# LED_indication.net
KiCad netlist of a schematic drawn in Altium Designer
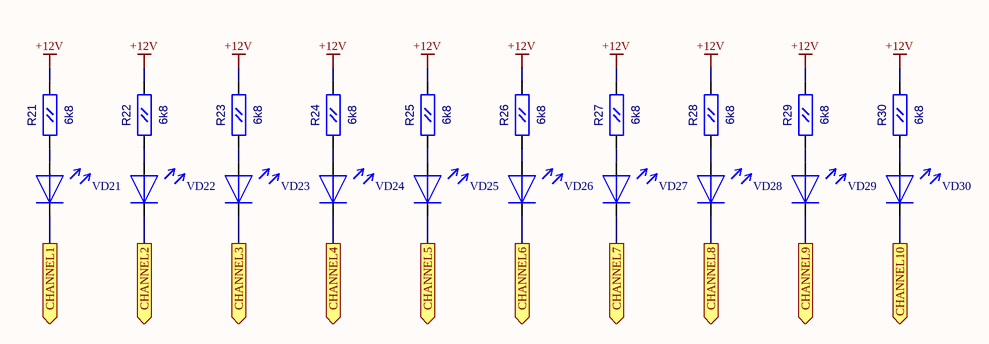
[diagram p0: LED_indication.SchDoc]

(export (version "E")
  (design (tool "Eeschema 10.0.6"))
  (components
    (comp (ref "R21")
      (value "6k8")
      (footprint "RC0603")
      (description "RC0603")
      (libsource (lib "gprs_modem_2") (part "RC0603"))
    )
    (comp (ref "R22")
      (value "6k8")
      (footprint "RC0603")
      (description "RC0603")
      (libsource (lib "gprs_modem_2") (part "RC0603"))
    )
    (comp (ref "R23")
      (value "6k8")
      (footprint "RC0603")
      (description "RC0603")
      (libsource (lib "gprs_modem_2") (part "RC0603"))
    )
    (comp (ref "R24")
      (value "6k8")
      (footprint "RC0603")
      (description "RC0603")
      (libsource (lib "gprs_modem_2") (part "RC0603"))
    )
    (comp (ref "R25")
      (value "6k8")
      (footprint "RC0603")
      (description "RC0603")
      (libsource (lib "gprs_modem_2") (part "RC0603"))
    )
    (comp (ref "R26")
      (value "6k8")
      (footprint "RC0603")
      (description "RC0603")
      (libsource (lib "gprs_modem_2") (part "RC0603"))
    )
    (comp (ref "R27")
      (value "6k8")
      (footprint "RC0603")
      (description "RC0603")
      (libsource (lib "gprs_modem_2") (part "RC0603"))
    )
    (comp (ref "R28")
      (value "6k8")
      (footprint "RC0603")
      (description "RC0603")
      (libsource (lib "gprs_modem_2") (part "RC0603"))
    )
    (comp (ref "R29")
      (value "6k8")
      (footprint "RC0603")
      (description "RC0603")
      (libsource (lib "gprs_modem_2") (part "RC0603"))
    )
    (comp (ref "R30")
      (value "6k8")
      (footprint "RC0603")
      (description "RC0603")
      (libsource (lib "gprs_modem_2") (part "RC0603"))
    )
    (comp (ref "VD21")
      (value "BL-HS135A-TRB")
      (footprint "LED0805")
      (libsource (lib "gprs_modem_2") (part "LED_0805"))
    )
    (comp (ref "VD22")
      (value "BL-HS135A-TRB")
      (footprint "LED0805")
      (libsource (lib "gprs_modem_2") (part "LED_0805"))
    )
    (comp (ref "VD23")
      (value "BL-HS135A-TRB")
      (footprint "LED0805")
      (libsource (lib "gprs_modem_2") (part "LED_0805"))
    )
    (comp (ref "VD24")
      (value "BL-HS135A-TRB")
      (footprint "LED0805")
      (libsource (lib "gprs_modem_2") (part "LED_0805"))
    )
    (comp (ref "VD25")
      (value "BL-HS135A-TRB")
      (footprint "LED0805")
      (libsource (lib "gprs_modem_2") (part "LED_0805"))
    )
    (comp (ref "VD26")
      (value "BL-HS135A-TRB")
      (footprint "LED0805")
      (libsource (lib "gprs_modem_2") (part "LED_0805"))
    )
    (comp (ref "VD27")
      (value "BL-HS135A-TRB")
      (footprint "LED0805")
      (libsource (lib "gprs_modem_2") (part "LED_0805"))
    )
    (comp (ref "VD28")
      (value "BL-HS135A-TRB")
      (footprint "LED0805")
      (libsource (lib "gprs_modem_2") (part "LED_0805"))
    )
    (comp (ref "VD29")
      (value "BL-HS135A-TRB")
      (footprint "LED0805")
      (libsource (lib "gprs_modem_2") (part "LED_0805"))
    )
    (comp (ref "VD30")
      (value "BL-HS135A-TRB")
      (footprint "LED0805")
      (libsource (lib "gprs_modem_2") (part "LED_0805"))
    )
  )
  (nets
    (net (code "1") (name "+12V") (class "Default")
      (node (ref "R21") (pin "2") (pinfunction "B_2") (pintype "passive"))
      (node (ref "R22") (pin "2") (pinfunction "B_2") (pintype "passive"))
      (node (ref "R23") (pin "2") (pinfunction "B_2") (pintype "passive"))
      (node (ref "R24") (pin "2") (pinfunction "B_2") (pintype "passive"))
      (node (ref "R25") (pin "2") (pinfunction "B_2") (pintype "passive"))
      (node (ref "R26") (pin "2") (pinfunction "B_2") (pintype "passive"))
      (node (ref "R27") (pin "2") (pinfunction "B_2") (pintype "passive"))
      (node (ref "R28") (pin "2") (pinfunction "B_2") (pintype "passive"))
      (node (ref "R29") (pin "2") (pinfunction "B_2") (pintype "passive"))
      (node (ref "R30") (pin "2") (pinfunction "B_2") (pintype "passive"))
    )
    (net (code "2") (name "/CHANNEL1") (class "Default") (node (ref "VD21") (pin "2") (pintype "passive")))
    (net (code "3") (name "/CHANNEL2") (class "Default") (node (ref "VD22") (pin "2") (pintype "passive")))
    (net (code "4") (name "/CHANNEL3") (class "Default") (node (ref "VD23") (pin "2") (pintype "passive")))
    (net (code "5") (name "/CHANNEL4") (class "Default") (node (ref "VD24") (pin "2") (pintype "passive")))
    (net (code "6") (name "/CHANNEL5") (class "Default") (node (ref "VD25") (pin "2") (pintype "passive")))
    (net (code "7") (name "/CHANNEL6") (class "Default") (node (ref "VD26") (pin "2") (pintype "passive")))
    (net (code "8") (name "/CHANNEL7") (class "Default") (node (ref "VD27") (pin "2") (pintype "passive")))
    (net (code "9") (name "/CHANNEL8") (class "Default") (node (ref "VD28") (pin "2") (pintype "passive")))
    (net (code "10") (name "/CHANNEL9") (class "Default") (node (ref "VD29") (pin "2") (pintype "passive")))
    (net (code "11") (name "/CHANNEL10") (class "Default") (node (ref "VD30") (pin "2") (pintype "passive")))
    (net (code "12") (name "Net-(R21-A)") (class "Default")
      (node (ref "R21") (pin "1") (pinfunction "A_1") (pintype "passive"))
      (node (ref "VD21") (pin "1") (pintype "passive"))
    )
    (net (code "13") (name "Net-(R22-A)") (class "Default")
      (node (ref "R22") (pin "1") (pinfunction "A_1") (pintype "passive"))
      (node (ref "VD22") (pin "1") (pintype "passive"))
    )
    (net (code "14") (name "Net-(R23-A)") (class "Default")
      (node (ref "R23") (pin "1") (pinfunction "A_1") (pintype "passive"))
      (node (ref "VD23") (pin "1") (pintype "passive"))
    )
    (net (code "15") (name "Net-(R24-A)") (class "Default")
      (node (ref "R24") (pin "1") (pinfunction "A_1") (pintype "passive"))
      (node (ref "VD24") (pin "1") (pintype "passive"))
    )
    (net (code "16") (name "Net-(R25-A)") (class "Default")
      (node (ref "R25") (pin "1") (pinfunction "A_1") (pintype "passive"))
      (node (ref "VD25") (pin "1") (pintype "passive"))
    )
    (net (code "17") (name "Net-(R26-A)") (class "Default")
      (node (ref "R26") (pin "1") (pinfunction "A_1") (pintype "passive"))
      (node (ref "VD26") (pin "1") (pintype "passive"))
    )
    (net (code "18") (name "Net-(R27-A)") (class "Default")
      (node (ref "R27") (pin "1") (pinfunction "A_1") (pintype "passive"))
      (node (ref "VD27") (pin "1") (pintype "passive"))
    )
    (net (code "19") (name "Net-(R28-A)") (class "Default")
      (node (ref "R28") (pin "1") (pinfunction "A_1") (pintype "passive"))
      (node (ref "VD28") (pin "1") (pintype "passive"))
    )
    (net (code "20") (name "Net-(R29-A)") (class "Default")
      (node (ref "R29") (pin "1") (pinfunction "A_1") (pintype "passive"))
      (node (ref "VD29") (pin "1") (pintype "passive"))
    )
    (net (code "21") (name "Net-(R30-A)") (class "Default")
      (node (ref "R30") (pin "1") (pinfunction "A_1") (pintype "passive"))
      (node (ref "VD30") (pin "1") (pintype "passive"))
    )
  )
)
